# wand_alpha.net
KiCad netlist of a schematic drawn in EAGLE
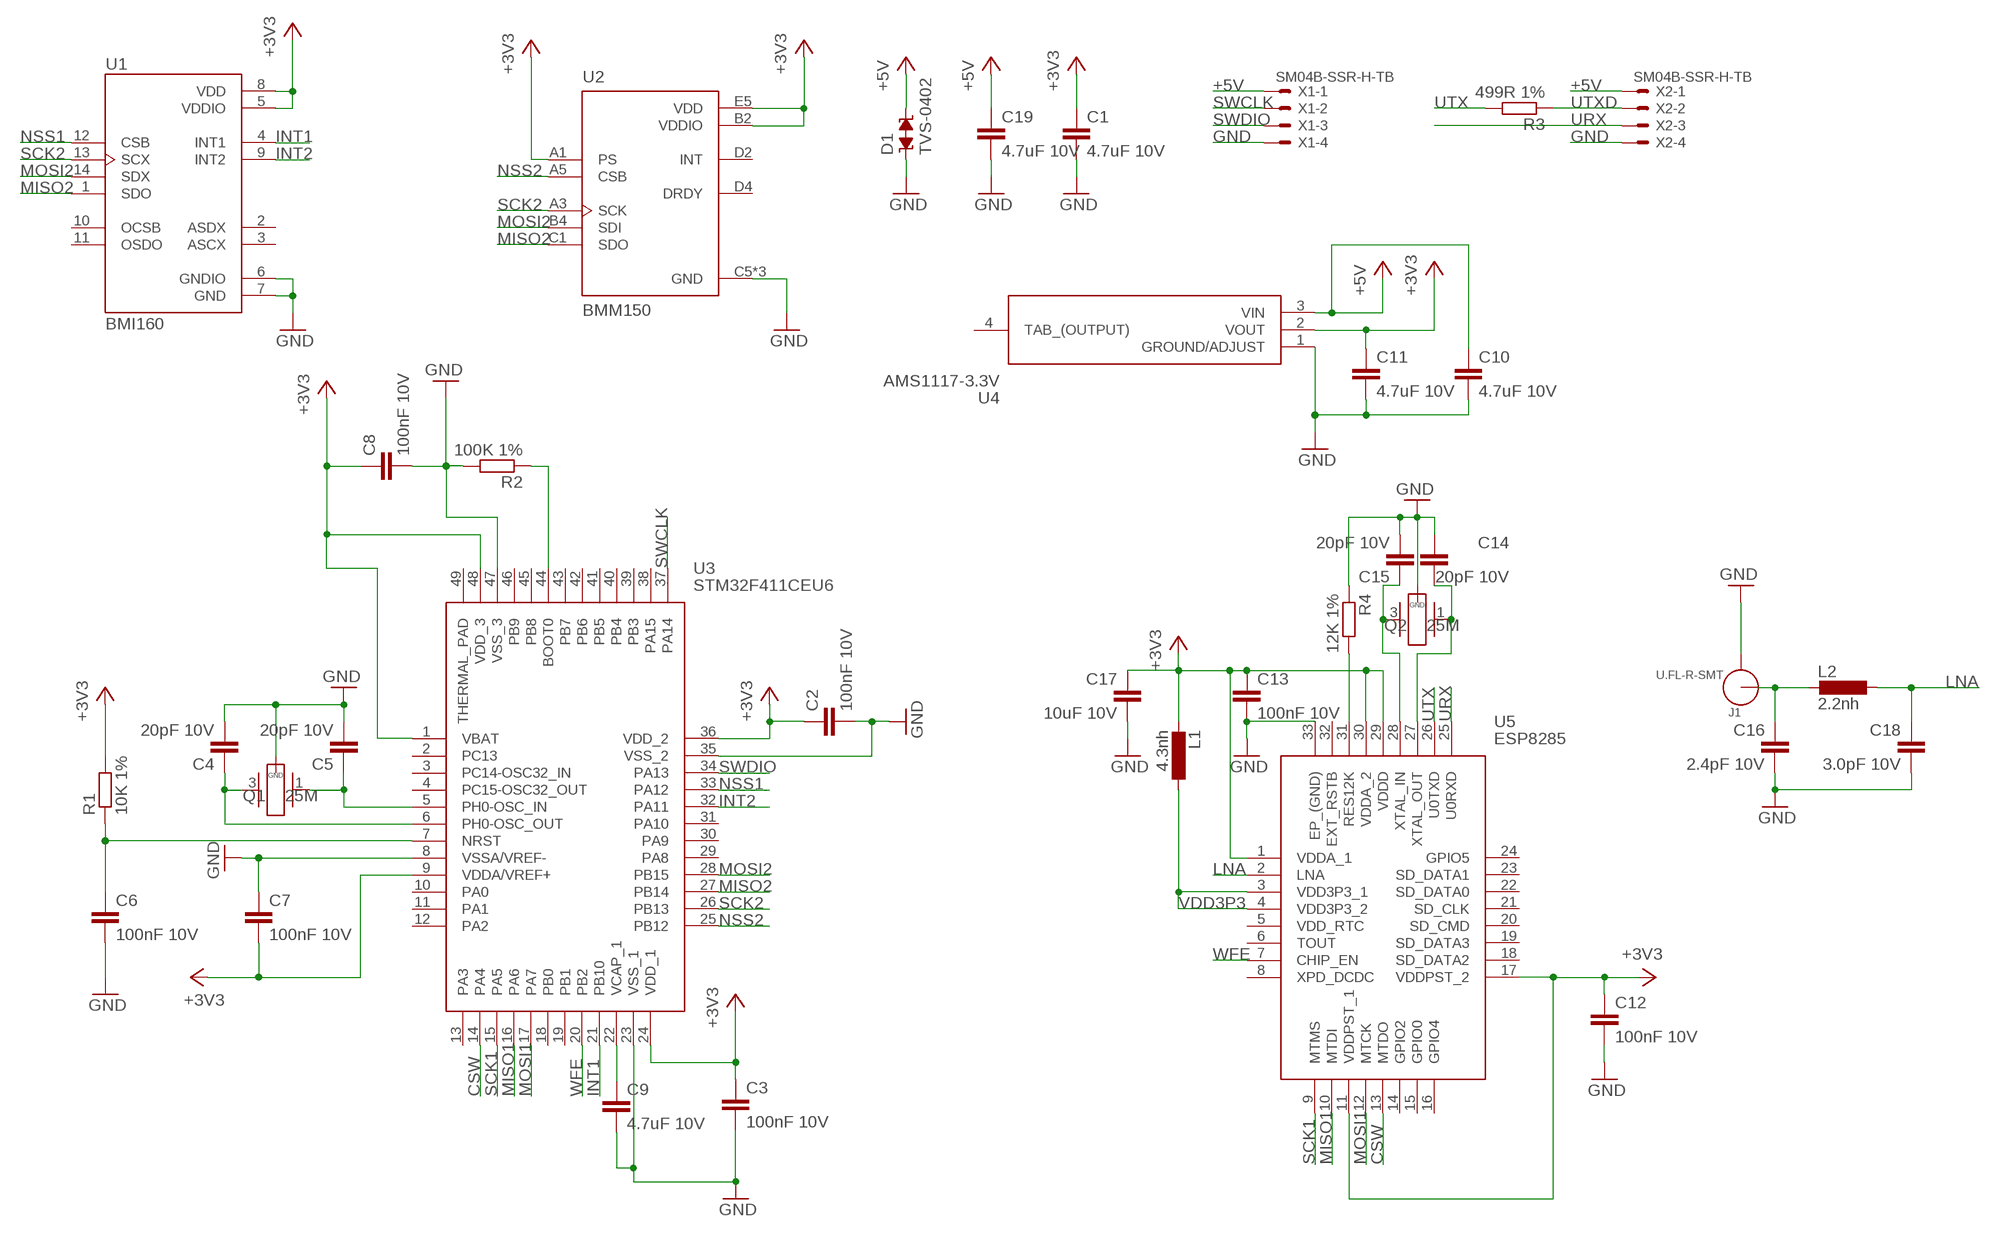
[diagram p0: schematic, sheet 1]

(export (version "E")
  (design (tool "Eeschema 10.0.6"))
  (components
    (comp (ref "C1")
      (value "4.7uF 10V")
      (footprint "eagle-import:C0402")
      (libsource (lib "eagle-import") (part "C-EUC0402"))
    )
    (comp (ref "C2")
      (value "100nF 10V")
      (footprint "eagle-import:C0402")
      (libsource (lib "eagle-import") (part "C-EUC0402"))
    )
    (comp (ref "C3")
      (value "100nF 10V")
      (footprint "eagle-import:C0402")
      (libsource (lib "eagle-import") (part "C-EUC0402"))
    )
    (comp (ref "C4")
      (value "20pF 10V")
      (footprint "eagle-import:C0402")
      (libsource (lib "eagle-import") (part "C-EUC0402"))
    )
    (comp (ref "C5")
      (value "20pF 10V")
      (footprint "eagle-import:C0402")
      (libsource (lib "eagle-import") (part "C-EUC0402"))
    )
    (comp (ref "C6")
      (value "100nF 10V")
      (footprint "eagle-import:C0402")
      (libsource (lib "eagle-import") (part "C-EUC0402"))
    )
    (comp (ref "C7")
      (value "100nF 10V")
      (footprint "eagle-import:C0402")
      (libsource (lib "eagle-import") (part "C-EUC0402"))
    )
    (comp (ref "C8")
      (value "100nF 10V")
      (footprint "eagle-import:C0402")
      (libsource (lib "eagle-import") (part "C-EUC0402"))
    )
    (comp (ref "C9")
      (value "4.7uF 10V")
      (footprint "eagle-import:C0402")
      (libsource (lib "eagle-import") (part "C-EUC0402"))
    )
    (comp (ref "C10")
      (value "4.7uF 10V")
      (footprint "eagle-import:C0402")
      (libsource (lib "eagle-import") (part "C-EUC0402"))
    )
    (comp (ref "C11")
      (value "4.7uF 10V")
      (footprint "eagle-import:C0402")
      (libsource (lib "eagle-import") (part "C-EUC0402"))
    )
    (comp (ref "C12")
      (value "100nF 10V")
      (footprint "eagle-import:C0402")
      (libsource (lib "eagle-import") (part "C-EUC0402"))
    )
    (comp (ref "C13")
      (value "100nF 10V")
      (footprint "eagle-import:C0402")
      (libsource (lib "eagle-import") (part "C-EUC0402"))
    )
    (comp (ref "C14")
      (value "20pF 10V")
      (footprint "eagle-import:C0402")
      (libsource (lib "eagle-import") (part "C-EUC0402"))
    )
    (comp (ref "C15")
      (value "20pF 10V")
      (footprint "eagle-import:C0402")
      (libsource (lib "eagle-import") (part "C-EUC0402"))
    )
    (comp (ref "C16")
      (value "2.4pF 10V")
      (footprint "eagle-import:C0402")
      (libsource (lib "eagle-import") (part "C-EUC0402"))
    )
    (comp (ref "C17")
      (value "10uF 10V")
      (footprint "eagle-import:C0402")
      (libsource (lib "eagle-import") (part "C-EUC0402"))
    )
    (comp (ref "C18")
      (value "3.0pF 10V")
      (footprint "eagle-import:C0402")
      (libsource (lib "eagle-import") (part "C-EUC0402"))
    )
    (comp (ref "C19")
      (value "4.7uF 10V")
      (footprint "eagle-import:C0402")
      (libsource (lib "eagle-import") (part "C-EUC0402"))
    )
    (comp (ref "D1")
      (value "TVS-0402")
      (footprint "eagle-import:TVS0402")
      (libsource (lib "eagle-import") (part "TVS-0402"))
    )
    (comp (ref "J1")
      (value "U.FL-R-SMT")
      (footprint "eagle-import:U.FL_SMT")
      (fields (field (name "MANUFACTURER") "Hirose") (field (name "MPN") "U.FL-R-SMT-1(01)"))
      (libsource (lib "eagle-import") (part "U.FL-R-SMT"))
    )
    (comp (ref "L1")
      (value "4.3nh")
      (footprint "eagle-import:L0402")
      (libsource (lib "eagle-import") (part "L-EUL0402"))
    )
    (comp (ref "L2")
      (value "2.2nh")
      (footprint "eagle-import:L0402")
      (libsource (lib "eagle-import") (part "L-EUL0402"))
    )
    (comp (ref "Q1")
      (value "25M")
      (footprint "eagle-import:FA-128")
      (libsource (lib "eagle-import") (part "FA-128"))
    )
    (comp (ref "Q2")
      (value "25M")
      (footprint "eagle-import:FA-128")
      (libsource (lib "eagle-import") (part "FA-128"))
    )
    (comp (ref "R1")
      (value "10K 1%")
      (footprint "eagle-import:R0402")
      (libsource (lib "eagle-import") (part "R-EU_R0402"))
    )
    (comp (ref "R2")
      (value "100K 1%")
      (footprint "eagle-import:R0402")
      (libsource (lib "eagle-import") (part "R-EU_R0402"))
    )
    (comp (ref "R3")
      (value "499R 1%")
      (footprint "eagle-import:R0402")
      (libsource (lib "eagle-import") (part "R-EU_R0402"))
    )
    (comp (ref "R4")
      (value "12K 1%")
      (footprint "eagle-import:R0402")
      (libsource (lib "eagle-import") (part "R-EU_R0402"))
    )
    (comp (ref "U1")
      (value "BMI160")
      (footprint "eagle-import:PQFN50P300X250X88-14N")
      (fields (field (name "MF") "Bosch"))
      (libsource (lib "eagle-import") (part "BMI160"))
    )
    (comp (ref "U2")
      (value "BMM150")
      (footprint "eagle-import:XDCR_BMM150")
      (fields (field (name "MF") "Bosch Sensortec"))
      (libsource (lib "eagle-import") (part "BMM150"))
    )
    (comp (ref "U3")
      (value "STM32F411CEU6")
      (footprint "eagle-import:QFN50P700X700X60-49N")
      (fields (field (name "MOUSER_PART_NUMBER") "511-STM32F411CEU6"))
      (libsource (lib "eagle-import") (part "STM32F411CEU6"))
    )
    (comp (ref "U4")
      (value "AMS1117-3.3V")
      (footprint "eagle-import:SOT229P700X180-4N")
      (fields (field (name "MANUFACTURER_PART_NUMBER") "ams1117-3.3v"))
      (libsource (lib "eagle-import") (part "AMS1117-3.3V"))
    )
    (comp (ref "U5")
      (value "ESP8285")
      (footprint "eagle-import:QFN50P500X500X90-33N")
      (fields (field (name "MOUSER_PART_NUMBER") "356-ESP8285"))
      (libsource (lib "eagle-import") (part "ESP8285"))
    )
    (comp (ref "X1")
      (value "SM04B-SSR-H-TB")
      (footprint "eagle-import:SM04B-SSR-H-TB")
      (libsource (lib "eagle-import") (part "SM04B-SSR-H-TB"))
    )
    (comp (ref "X2")
      (value "SM04B-SSR-H-TB")
      (footprint "eagle-import:SM04B-SSR-H-TB")
      (libsource (lib "eagle-import") (part "SM04B-SSR-H-TB"))
    )
  )
  (nets
    (net (code "1") (name "+3V3") (class "Default")
      (node (ref "C1") (pin "1") (pinfunction "1_1") (pintype "passive"))
      (node (ref "C11") (pin "1") (pinfunction "1_1") (pintype "passive"))
      (node (ref "C12") (pin "1") (pinfunction "1_1") (pintype "passive"))
      (node (ref "C13") (pin "1") (pinfunction "1_1") (pintype "passive"))
      (node (ref "C17") (pin "1") (pinfunction "1_1") (pintype "passive"))
      (node (ref "C2") (pin "1") (pinfunction "1_1") (pintype "passive"))
      (node (ref "C3") (pin "1") (pinfunction "1_1") (pintype "passive"))
      (node (ref "C7") (pin "2") (pinfunction "2_2") (pintype "passive"))
      (node (ref "C8") (pin "1") (pinfunction "1_1") (pintype "passive"))
      (node (ref "L1") (pin "2") (pinfunction "2_2") (pintype "passive"))
      (node (ref "R1") (pin "2") (pinfunction "2_2") (pintype "passive"))
      (node (ref "U1") (pin "5") (pinfunction "VDDIO_5") (pintype "power_in"))
      (node (ref "U1") (pin "8") (pinfunction "VDD_8") (pintype "power_in"))
      (node (ref "U2") (pin "A1") (pinfunction "PS_A1") (pintype "input"))
      (node (ref "U2") (pin "B2") (pinfunction "VDDIO_B2") (pintype "power_in"))
      (node (ref "U2") (pin "E5") (pinfunction "VDD_E5") (pintype "power_in"))
      (node (ref "U3") (pin "1") (pinfunction "VBAT_1") (pintype "bidirectional"))
      (node (ref "U3") (pin "24") (pinfunction "VDD_1_24") (pintype "bidirectional"))
      (node (ref "U3") (pin "36") (pinfunction "VDD_2_36") (pintype "bidirectional"))
      (node (ref "U3") (pin "48") (pinfunction "VDD_3_48") (pintype "bidirectional"))
      (node (ref "U3") (pin "9") (pinfunction "VDDA/VREF+_9") (pintype "bidirectional"))
      (node (ref "U4") (pin "2") (pinfunction "VOUT_2") (pintype "bidirectional"))
      (node (ref "U5") (pin "1") (pinfunction "VDDA_1_1") (pintype "bidirectional"))
      (node (ref "U5") (pin "11") (pinfunction "VDDPST_1_11") (pintype "bidirectional"))
      (node (ref "U5") (pin "17") (pinfunction "VDDPST_2_17") (pintype "bidirectional"))
      (node (ref "U5") (pin "29") (pinfunction "VDDD_29") (pintype "bidirectional"))
      (node (ref "U5") (pin "30") (pinfunction "VDDA_2_30") (pintype "bidirectional"))
    )
    (net (code "2") (name "+5V") (class "Default")
      (node (ref "C10") (pin "1") (pinfunction "1_1") (pintype "passive"))
      (node (ref "C19") (pin "1") (pinfunction "1_1") (pintype "passive"))
      (node (ref "D1") (pin "2") (pinfunction "2_2") (pintype "passive"))
      (node (ref "U4") (pin "3") (pinfunction "VIN_3") (pintype "bidirectional"))
      (node (ref "X1") (pin "1") (pinfunction "S_1") (pintype "passive"))
      (node (ref "X2") (pin "1") (pinfunction "S_1") (pintype "passive"))
    )
    (net (code "3") (name "/CSW") (class "Default")
      (node (ref "U3") (pin "14") (pinfunction "PA4_14") (pintype "bidirectional"))
      (node (ref "U5") (pin "13") (pinfunction "MTDO_13") (pintype "bidirectional"))
    )
    (net (code "4") (name "/INT1") (class "Default")
      (node (ref "U1") (pin "4") (pinfunction "INT1_4") (pintype "bidirectional"))
      (node (ref "U3") (pin "21") (pinfunction "PB10_21") (pintype "bidirectional"))
    )
    (net (code "5") (name "/INT2") (class "Default")
      (node (ref "U1") (pin "9") (pinfunction "INT2_9") (pintype "bidirectional"))
      (node (ref "U3") (pin "32") (pinfunction "PA11_32") (pintype "bidirectional"))
    )
    (net (code "6") (name "/LNA") (class "Default")
      (node (ref "C18") (pin "1") (pinfunction "1_1") (pintype "passive"))
      (node (ref "L2") (pin "1") (pinfunction "1_1") (pintype "passive"))
      (node (ref "U5") (pin "2") (pinfunction "LNA_2") (pintype "bidirectional"))
    )
    (net (code "7") (name "/MISO1") (class "Default")
      (node (ref "U3") (pin "16") (pinfunction "PA6_16") (pintype "bidirectional"))
      (node (ref "U5") (pin "10") (pinfunction "MTDI_10") (pintype "bidirectional"))
    )
    (net (code "8") (name "/MISO2") (class "Default")
      (node (ref "U1") (pin "1") (pinfunction "SDO_1") (pintype "bidirectional"))
      (node (ref "U2") (pin "C1") (pinfunction "SDO_C1") (pintype "output"))
      (node (ref "U3") (pin "27") (pinfunction "PB14_27") (pintype "bidirectional"))
    )
    (net (code "9") (name "/MOSI1") (class "Default")
      (node (ref "U3") (pin "17") (pinfunction "PA7_17") (pintype "bidirectional"))
      (node (ref "U5") (pin "12") (pinfunction "MTCK_12") (pintype "bidirectional"))
    )
    (net (code "10") (name "/MOSI2") (class "Default")
      (node (ref "U1") (pin "14") (pinfunction "SDX_14") (pintype "bidirectional"))
      (node (ref "U2") (pin "B4") (pinfunction "SDI_B4") (pintype "bidirectional"))
      (node (ref "U3") (pin "28") (pinfunction "PB15_28") (pintype "bidirectional"))
    )
    (net (code "11") (name "/NSS1") (class "Default")
      (node (ref "U1") (pin "12") (pinfunction "CSB_12") (pintype "input"))
      (node (ref "U3") (pin "33") (pinfunction "PA12_33") (pintype "bidirectional"))
    )
    (net (code "12") (name "/NSS2") (class "Default")
      (node (ref "U2") (pin "A5") (pinfunction "CSB_A5") (pintype "input"))
      (node (ref "U3") (pin "25") (pinfunction "PB12_25") (pintype "bidirectional"))
    )
    (net (code "13") (name "/SCK1") (class "Default")
      (node (ref "U3") (pin "15") (pinfunction "PA5_15") (pintype "bidirectional"))
      (node (ref "U5") (pin "9") (pinfunction "MTMS_9") (pintype "bidirectional"))
    )
    (net (code "14") (name "/SCK2") (class "Default")
      (node (ref "U1") (pin "13") (pinfunction "SCX_13") (pintype "input"))
      (node (ref "U2") (pin "A3") (pinfunction "SCK_A3") (pintype "input"))
      (node (ref "U3") (pin "26") (pinfunction "PB13_26") (pintype "bidirectional"))
    )
    (net (code "15") (name "/SWCLK") (class "Default")
      (node (ref "U3") (pin "37") (pinfunction "PA14_37") (pintype "bidirectional"))
      (node (ref "X1") (pin "2") (pinfunction "S_2") (pintype "passive"))
    )
    (net (code "16") (name "/SWDIO") (class "Default")
      (node (ref "U3") (pin "34") (pinfunction "PA13_34") (pintype "bidirectional"))
      (node (ref "X1") (pin "3") (pinfunction "S_3") (pintype "passive"))
    )
    (net (code "17") (name "/URX") (class "Default")
      (node (ref "U5") (pin "25") (pinfunction "U0RXD_25") (pintype "bidirectional"))
      (node (ref "X2") (pin "3") (pinfunction "S_3") (pintype "passive"))
    )
    (net (code "18") (name "/UTX") (class "Default")
      (node (ref "R3") (pin "2") (pinfunction "2_2") (pintype "passive"))
      (node (ref "U5") (pin "26") (pinfunction "U0TXD_26") (pintype "bidirectional"))
    )
    (net (code "19") (name "/UTXD") (class "Default")
      (node (ref "R3") (pin "1") (pinfunction "1_1") (pintype "passive"))
      (node (ref "X2") (pin "2") (pinfunction "S_2") (pintype "passive"))
    )
    (net (code "20") (name "/VDD3P3") (class "Default")
      (node (ref "L1") (pin "1") (pinfunction "1_1") (pintype "passive"))
      (node (ref "U5") (pin "3") (pinfunction "VDD3P3_1_3") (pintype "bidirectional"))
      (node (ref "U5") (pin "4") (pinfunction "VDD3P3_2_4") (pintype "bidirectional"))
    )
    (net (code "21") (name "/WFE") (class "Default")
      (node (ref "U3") (pin "20") (pinfunction "PB2_20") (pintype "bidirectional"))
      (node (ref "U5") (pin "7") (pinfunction "CHIP_EN_7") (pintype "bidirectional"))
    )
    (net (code "22") (name "GND") (class "Default")
      (node (ref "C1") (pin "2") (pinfunction "2_2") (pintype "passive"))
      (node (ref "C10") (pin "2") (pinfunction "2_2") (pintype "passive"))
      (node (ref "C11") (pin "2") (pinfunction "2_2") (pintype "passive"))
      (node (ref "C12") (pin "2") (pinfunction "2_2") (pintype "passive"))
      (node (ref "C13") (pin "2") (pinfunction "2_2") (pintype "passive"))
      (node (ref "C14") (pin "2") (pinfunction "2_2") (pintype "passive"))
      (node (ref "C15") (pin "2") (pinfunction "2_2") (pintype "passive"))
      (node (ref "C16") (pin "2") (pinfunction "2_2") (pintype "passive"))
      (node (ref "C17") (pin "2") (pinfunction "2_2") (pintype "passive"))
      (node (ref "C18") (pin "2") (pinfunction "2_2") (pintype "passive"))
      (node (ref "C19") (pin "2") (pinfunction "2_2") (pintype "passive"))
      (node (ref "C2") (pin "2") (pinfunction "2_2") (pintype "passive"))
      (node (ref "C3") (pin "2") (pinfunction "2_2") (pintype "passive"))
      (node (ref "C4") (pin "2") (pinfunction "2_2") (pintype "passive"))
      (node (ref "C5") (pin "2") (pinfunction "2_2") (pintype "passive"))
      (node (ref "C6") (pin "2") (pinfunction "2_2") (pintype "passive"))
      (node (ref "C7") (pin "1") (pinfunction "1_1") (pintype "passive"))
      (node (ref "C8") (pin "2") (pinfunction "2_2") (pintype "passive"))
      (node (ref "C9") (pin "2") (pinfunction "2_2") (pintype "passive"))
      (node (ref "D1") (pin "1") (pinfunction "1_1") (pintype "passive"))
      (node (ref "J1") (pin "GND1") (pinfunction "P$2_GND1") (pintype "bidirectional"))
      (node (ref "J1") (pin "GND2") (pinfunction "P$2_GND2") (pintype "bidirectional"))
      (node (ref "Q1") (pin "2") (pinfunction "GND_2") (pintype "bidirectional"))
      (node (ref "Q1") (pin "4") (pinfunction "GND_4") (pintype "bidirectional"))
      (node (ref "Q2") (pin "2") (pinfunction "GND_2") (pintype "bidirectional"))
      (node (ref "Q2") (pin "4") (pinfunction "GND_4") (pintype "bidirectional"))
      (node (ref "R2") (pin "2") (pinfunction "2_2") (pintype "passive"))
      (node (ref "R4") (pin "1") (pinfunction "1_1") (pintype "passive"))
      (node (ref "U1") (pin "6") (pinfunction "GNDIO_6") (pintype "power_in"))
      (node (ref "U1") (pin "7") (pinfunction "GND_7") (pintype "power_in"))
      (node (ref "U2") (pin "C5") (pinfunction "GND_C5") (pintype "power_in"))
      (node (ref "U2") (pin "E1") (pinfunction "GND_E1") (pintype "power_in"))
      (node (ref "U2") (pin "E3") (pinfunction "GND_E3") (pintype "power_in"))
      (node (ref "U3") (pin "23") (pinfunction "VSS_1_23") (pintype "bidirectional"))
      (node (ref "U3") (pin "35") (pinfunction "VSS_2_35") (pintype "bidirectional"))
      (node (ref "U3") (pin "47") (pinfunction "VSS_3_47") (pintype "bidirectional"))
      (node (ref "U3") (pin "8") (pinfunction "VSSA/VREF-_8") (pintype "bidirectional"))
      (node (ref "U4") (pin "1") (pinfunction "GROUND/ADJUST_1") (pintype "bidirectional"))
      (node (ref "U5") (pin "33") (pinfunction "EP_(GND)_33") (pintype "bidirectional"))
      (node (ref "X1") (pin "4") (pinfunction "S_4") (pintype "passive"))
      (node (ref "X2") (pin "4") (pinfunction "S_4") (pintype "passive"))
    )
    (net (code "23") (name "Net-(J1-ANT)") (class "Default")
      (node (ref "C16") (pin "1") (pinfunction "1_1") (pintype "passive"))
      (node (ref "J1") (pin "SIG") (pinfunction "ANT_SIG") (pintype "bidirectional"))
      (node (ref "L2") (pin "2") (pinfunction "2_2") (pintype "passive"))
    )
    (net (code "24") (name "Net-(Q1-2)") (class "Default")
      (node (ref "C4") (pin "1") (pinfunction "1_1") (pintype "passive"))
      (node (ref "Q1") (pin "3") (pinfunction "2_3") (pintype "bidirectional"))
      (node (ref "U3") (pin "6") (pinfunction "PH0-OSC_OUT_6") (pintype "bidirectional"))
    )
    (net (code "25") (name "Net-(Q2-2)") (class "Default")
      (node (ref "C15") (pin "1") (pinfunction "1_1") (pintype "passive"))
      (node (ref "Q2") (pin "3") (pinfunction "2_3") (pintype "bidirectional"))
      (node (ref "U5") (pin "28") (pinfunction "XTAL_IN_28") (pintype "bidirectional"))
    )
    (net (code "26") (name "Net-(U3-BOOT0)") (class "Default")
      (node (ref "R2") (pin "1") (pinfunction "1_1") (pintype "passive"))
      (node (ref "U3") (pin "44") (pinfunction "BOOT0_44") (pintype "bidirectional"))
    )
    (net (code "27") (name "Net-(U3-NRST)") (class "Default")
      (node (ref "C6") (pin "1") (pinfunction "1_1") (pintype "passive"))
      (node (ref "R1") (pin "1") (pinfunction "1_1") (pintype "passive"))
      (node (ref "U3") (pin "7") (pinfunction "NRST_7") (pintype "bidirectional"))
    )
    (net (code "28") (name "Net-(U3-PH0-OSC_IN)") (class "Default")
      (node (ref "C5") (pin "1") (pinfunction "1_1") (pintype "passive"))
      (node (ref "Q1") (pin "1") (pinfunction "1_1") (pintype "bidirectional"))
      (node (ref "U3") (pin "5") (pinfunction "PH0-OSC_IN_5") (pintype "bidirectional"))
    )
    (net (code "29") (name "Net-(U3-VCAP_1)") (class "Default")
      (node (ref "C9") (pin "1") (pinfunction "1_1") (pintype "passive"))
      (node (ref "U3") (pin "22") (pinfunction "VCAP_1_22") (pintype "bidirectional"))
    )
    (net (code "30") (name "Net-(U5-RES12K)") (class "Default")
      (node (ref "R4") (pin "2") (pinfunction "2_2") (pintype "passive"))
      (node (ref "U5") (pin "31") (pinfunction "RES12K_31") (pintype "bidirectional"))
    )
    (net (code "31") (name "Net-(U5-XTAL_OUT)") (class "Default")
      (node (ref "C14") (pin "1") (pinfunction "1_1") (pintype "passive"))
      (node (ref "Q2") (pin "1") (pinfunction "1_1") (pintype "bidirectional"))
      (node (ref "U5") (pin "27") (pinfunction "XTAL_OUT_27") (pintype "bidirectional"))
    )
    (net (code "32") (name "unconnected-(U1-ASCX-Pad3)") (class "Default")
      (node (ref "U1") (pin "3") (pinfunction "ASCX_3") (pintype "output"))
    )
    (net (code "33") (name "unconnected-(U1-ASDX-Pad2)") (class "Default")
      (node (ref "U1") (pin "2") (pinfunction "ASDX_2") (pintype "bidirectional"))
    )
    (net (code "34") (name "unconnected-(U1-OCSB-Pad10)") (class "Default")
      (node (ref "U1") (pin "10") (pinfunction "OCSB_10") (pintype "bidirectional"))
    )
    (net (code "35") (name "unconnected-(U1-OSDO-Pad11)") (class "Default")
      (node (ref "U1") (pin "11") (pinfunction "OSDO_11") (pintype "bidirectional"))
    )
    (net (code "36") (name "unconnected-(U2-DRDY-PadD4)") (class "Default")
      (node (ref "U2") (pin "D4") (pinfunction "DRDY_D4") (pintype "output"))
    )
    (net (code "37") (name "unconnected-(U2-INT-PadD2)") (class "Default")
      (node (ref "U2") (pin "D2") (pinfunction "INT_D2") (pintype "output"))
    )
    (net (code "38") (name "unconnected-(U3-PA0-Pad10)") (class "Default")
      (node (ref "U3") (pin "10") (pinfunction "PA0_10") (pintype "bidirectional"))
    )
    (net (code "39") (name "unconnected-(U3-PA1-Pad11)") (class "Default")
      (node (ref "U3") (pin "11") (pinfunction "PA1_11") (pintype "bidirectional"))
    )
    (net (code "40") (name "unconnected-(U3-PA2-Pad12)") (class "Default")
      (node (ref "U3") (pin "12") (pinfunction "PA2_12") (pintype "bidirectional"))
    )
    (net (code "41") (name "unconnected-(U3-PA3-Pad13)") (class "Default")
      (node (ref "U3") (pin "13") (pinfunction "PA3_13") (pintype "bidirectional"))
    )
    (net (code "42") (name "unconnected-(U3-PA8-Pad29)") (class "Default")
      (node (ref "U3") (pin "29") (pinfunction "PA8_29") (pintype "bidirectional"))
    )
    (net (code "43") (name "unconnected-(U3-PA9-Pad30)") (class "Default")
      (node (ref "U3") (pin "30") (pinfunction "PA9_30") (pintype "bidirectional"))
    )
    (net (code "44") (name "unconnected-(U3-PA10-Pad31)") (class "Default")
      (node (ref "U3") (pin "31") (pinfunction "PA10_31") (pintype "bidirectional"))
    )
    (net (code "45") (name "unconnected-(U3-PA15-Pad38)") (class "Default")
      (node (ref "U3") (pin "38") (pinfunction "PA15_38") (pintype "bidirectional"))
    )
    (net (code "46") (name "unconnected-(U3-PB0-Pad18)") (class "Default")
      (node (ref "U3") (pin "18") (pinfunction "PB0_18") (pintype "bidirectional"))
    )
    (net (code "47") (name "unconnected-(U3-PB1-Pad19)") (class "Default")
      (node (ref "U3") (pin "19") (pinfunction "PB1_19") (pintype "bidirectional"))
    )
    (net (code "48") (name "unconnected-(U3-PB3-Pad39)") (class "Default")
      (node (ref "U3") (pin "39") (pinfunction "PB3_39") (pintype "bidirectional"))
    )
    (net (code "49") (name "unconnected-(U3-PB4-Pad40)") (class "Default")
      (node (ref "U3") (pin "40") (pinfunction "PB4_40") (pintype "bidirectional"))
    )
    (net (code "50") (name "unconnected-(U3-PB5-Pad41)") (class "Default")
      (node (ref "U3") (pin "41") (pinfunction "PB5_41") (pintype "bidirectional"))
    )
    (net (code "51") (name "unconnected-(U3-PB6-Pad42)") (class "Default")
      (node (ref "U3") (pin "42") (pinfunction "PB6_42") (pintype "bidirectional"))
    )
    (net (code "52") (name "unconnected-(U3-PB7-Pad43)") (class "Default")
      (node (ref "U3") (pin "43") (pinfunction "PB7_43") (pintype "bidirectional"))
    )
    (net (code "53") (name "unconnected-(U3-PB8-Pad45)") (class "Default")
      (node (ref "U3") (pin "45") (pinfunction "PB8_45") (pintype "bidirectional"))
    )
    (net (code "54") (name "unconnected-(U3-PB9-Pad46)") (class "Default")
      (node (ref "U3") (pin "46") (pinfunction "PB9_46") (pintype "bidirectional"))
    )
    (net (code "55") (name "unconnected-(U3-PC13-Pad2)") (class "Default")
      (node (ref "U3") (pin "2") (pinfunction "PC13_2") (pintype "bidirectional"))
    )
    (net (code "56") (name "unconnected-(U3-PC14-OSC32_IN-Pad3)") (class "Default")
      (node (ref "U3") (pin "3") (pinfunction "PC14-OSC32_IN_3") (pintype "bidirectional"))
    )
    (net (code "57") (name "unconnected-(U3-PC15-OSC32_OUT-Pad4)") (class "Default")
      (node (ref "U3") (pin "4") (pinfunction "PC15-OSC32_OUT_4") (pintype "bidirectional"))
    )
    (net (code "58") (name "unconnected-(U3-THERMAL_PAD-Pad49)") (class "Default")
      (node (ref "U3") (pin "49") (pinfunction "THERMAL_PAD_49") (pintype "bidirectional"))
    )
    (net (code "59") (name "unconnected-(U4-TAB_(OUTPUT)-Pad4)") (class "Default")
      (node (ref "U4") (pin "4") (pinfunction "TAB_(OUTPUT)_4") (pintype "bidirectional"))
    )
    (net (code "60") (name "unconnected-(U5-EXT_RSTB-Pad32)") (class "Default")
      (node (ref "U5") (pin "32") (pinfunction "EXT_RSTB_32") (pintype "bidirectional"))
    )
    (net (code "61") (name "unconnected-(U5-GPIO0-Pad15)") (class "Default")
      (node (ref "U5") (pin "15") (pinfunction "GPIO0_15") (pintype "bidirectional"))
    )
    (net (code "62") (name "unconnected-(U5-GPIO2-Pad14)") (class "Default")
      (node (ref "U5") (pin "14") (pinfunction "GPIO2_14") (pintype "bidirectional"))
    )
    (net (code "63") (name "unconnected-(U5-GPIO4-Pad16)") (class "Default")
      (node (ref "U5") (pin "16") (pinfunction "GPIO4_16") (pintype "bidirectional"))
    )
    (net (code "64") (name "unconnected-(U5-GPIO5-Pad24)") (class "Default")
      (node (ref "U5") (pin "24") (pinfunction "GPIO5_24") (pintype "bidirectional"))
    )
    (net (code "65") (name "unconnected-(U5-SD_CLK-Pad21)") (class "Default")
      (node (ref "U5") (pin "21") (pinfunction "SD_CLK_21") (pintype "bidirectional"))
    )
    (net (code "66") (name "unconnected-(U5-SD_CMD-Pad20)") (class "Default")
      (node (ref "U5") (pin "20") (pinfunction "SD_CMD_20") (pintype "bidirectional"))
    )
    (net (code "67") (name "unconnected-(U5-SD_DATA0-Pad22)") (class "Default")
      (node (ref "U5") (pin "22") (pinfunction "SD_DATA0_22") (pintype "bidirectional"))
    )
    (net (code "68") (name "unconnected-(U5-SD_DATA1-Pad23)") (class "Default")
      (node (ref "U5") (pin "23") (pinfunction "SD_DATA1_23") (pintype "bidirectional"))
    )
    (net (code "69") (name "unconnected-(U5-SD_DATA2-Pad18)") (class "Default")
      (node (ref "U5") (pin "18") (pinfunction "SD_DATA2_18") (pintype "bidirectional"))
    )
    (net (code "70") (name "unconnected-(U5-SD_DATA3-Pad19)") (class "Default")
      (node (ref "U5") (pin "19") (pinfunction "SD_DATA3_19") (pintype "bidirectional"))
    )
    (net (code "71") (name "unconnected-(U5-TOUT-Pad6)") (class "Default")
      (node (ref "U5") (pin "6") (pinfunction "TOUT_6") (pintype "bidirectional"))
    )
    (net (code "72") (name "unconnected-(U5-VDD_RTC-Pad5)") (class "Default")
      (node (ref "U5") (pin "5") (pinfunction "VDD_RTC_5") (pintype "bidirectional"))
    )
    (net (code "73") (name "unconnected-(U5-XPD_DCDC-Pad8)") (class "Default")
      (node (ref "U5") (pin "8") (pinfunction "XPD_DCDC_8") (pintype "bidirectional"))
    )
  )
)
